# Walrus_Radios.net
KiCad netlist of a schematic drawn in Altium Designer
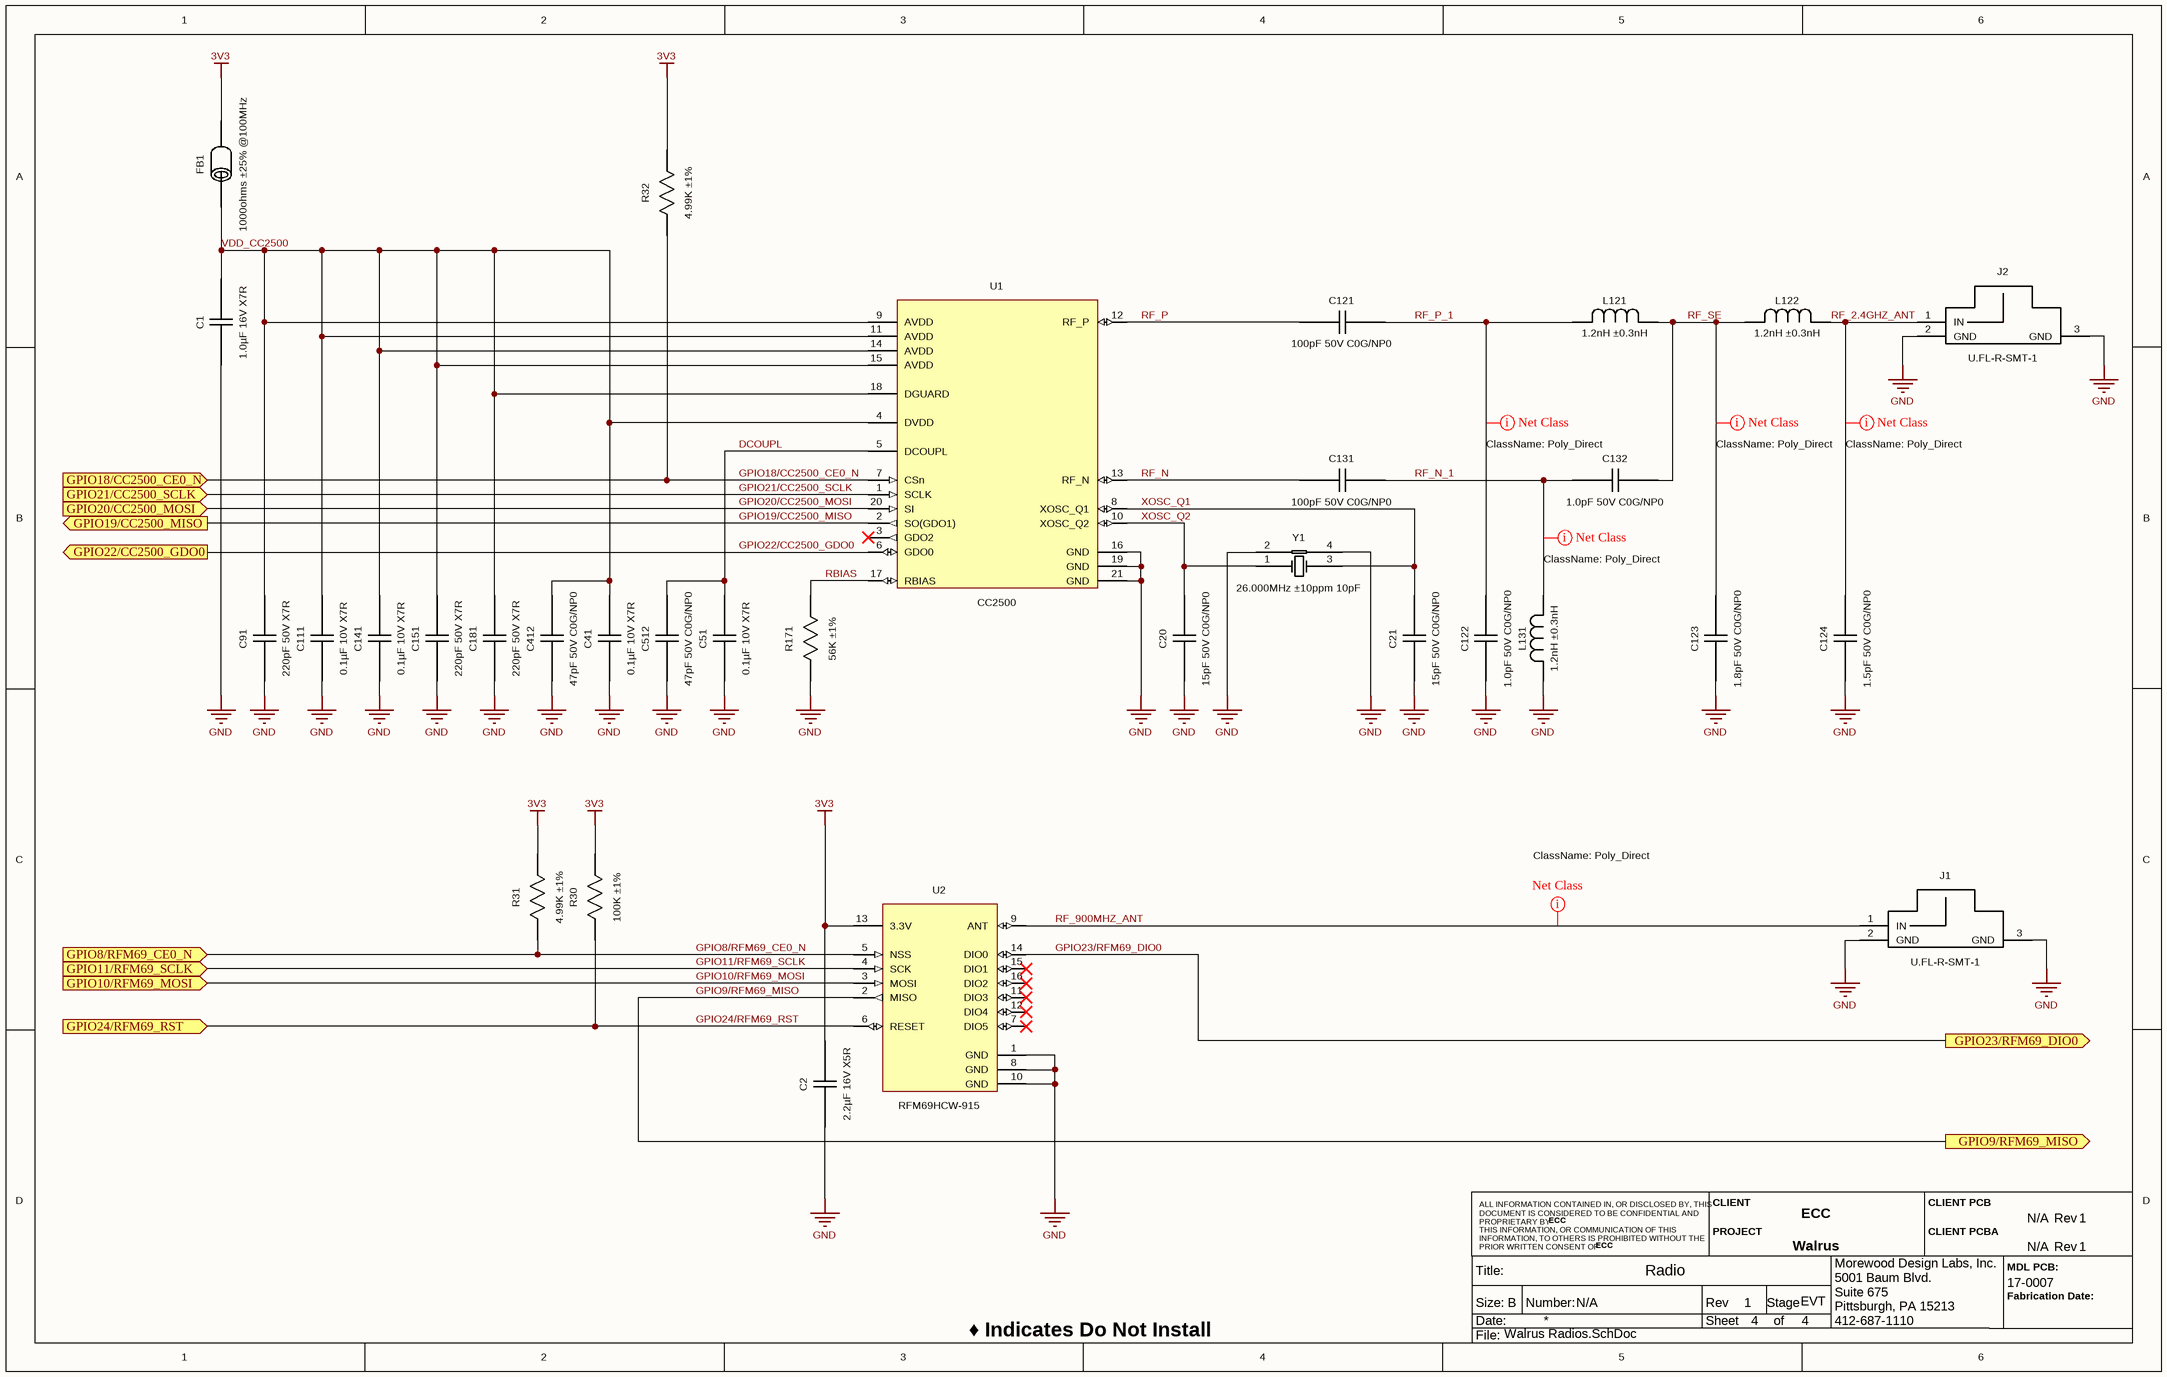
[diagram p0: Walrus Radios.SchDoc]

(export (version "E")
  (design (tool "Eeschema 10.0.6"))
  (components
    (comp (ref "C1")
      (value "1.0µF 16V X7R")
      (footprint "CAPC1608X90L(0603)")
      (description "Ceramic Chip Capacitor")
      (fields
        (field (name "MDLPARTNUMBER") "CAP_000045")
        (field (name "TOLERANCE") "±10%")
        (field (name "CREATOR") "R. Casciola")
      )
      (libsource (lib "Morewood Labs") (part "Capacitor 1"))
    )
    (comp (ref "C2")
      (value "2.2µF 16V X5R")
      (footprint "CAPC1005X60L(0402)")
      (description "Ceramic Chip Capacitor")
      (fields
        (field (name "MDLPARTNUMBER") "CAP_000166")
        (field (name "TOLERANCE") "±10%")
        (field (name "CREATOR") "R. Casciola")
      )
      (libsource (lib "Morewood Labs") (part "Capacitor 1"))
    )
    (comp (ref "C20")
      (value "15pF 50V C0G/NP0")
      (footprint "CAPC1005X60L(0402_FLEXTRONICS)")
      (description "Ceramic Chip Capacitor")
      (fields
        (field (name "MDLPARTNUMBER") "CAP_000179")
        (field (name "TOLERANCE") "±2%")
        (field (name "CREATOR") "R. Casciola")
        (field (name "MODIFER") "R. Casciola")
      )
      (libsource (lib "Morewood Labs") (part "Capacitor 1"))
    )
    (comp (ref "C21")
      (value "15pF 50V C0G/NP0")
      (footprint "CAPC1005X60L(0402_FLEXTRONICS)")
      (description "Ceramic Chip Capacitor")
      (fields
        (field (name "MDLPARTNUMBER") "CAP_000179")
        (field (name "TOLERANCE") "±2%")
        (field (name "CREATOR") "R. Casciola")
        (field (name "MODIFER") "R. Casciola")
      )
      (libsource (lib "Morewood Labs") (part "Capacitor 1"))
    )
    (comp (ref "C41")
      (value "0.1µF 10V X7R")
      (footprint "CAPC1005X60L(0402_FLEXTRONICS)")
      (description "Ceramic Chip Capacitor")
      (fields
        (field (name "MDLPARTNUMBER") "CAP_000208")
        (field (name "TOLERANCE") "±10%")
        (field (name "CREATOR") "R. Casciola")
      )
      (libsource (lib "Morewood Labs") (part "Capacitor 1"))
    )
    (comp (ref "C51")
      (value "0.1µF 10V X7R")
      (footprint "CAPC1005X60L(0402_FLEXTRONICS)")
      (description "Ceramic Chip Capacitor")
      (fields
        (field (name "MDLPARTNUMBER") "CAP_000208")
        (field (name "TOLERANCE") "±10%")
        (field (name "CREATOR") "R. Casciola")
      )
      (libsource (lib "Morewood Labs") (part "Capacitor 1"))
    )
    (comp (ref "C91")
      (value "220pF 50V X7R")
      (footprint "CAPC1005X60L(0402_FLEXTRONICS)")
      (description "Ceramic Chip Capacitor")
      (fields
        (field (name "MDLPARTNUMBER") "CAP_000207")
        (field (name "TOLERANCE") "±10%")
        (field (name "CREATOR") "R. Casciola")
      )
      (libsource (lib "Morewood Labs") (part "Capacitor 1"))
    )
    (comp (ref "C111")
      (value "0.1µF 10V X7R")
      (footprint "CAPC1005X60L(0402_FLEXTRONICS)")
      (description "Ceramic Chip Capacitor")
      (fields
        (field (name "MDLPARTNUMBER") "CAP_000208")
        (field (name "TOLERANCE") "±10%")
        (field (name "CREATOR") "R. Casciola")
      )
      (libsource (lib "Morewood Labs") (part "Capacitor 1"))
    )
    (comp (ref "C121")
      (value "100pF 50V C0G/NP0")
      (footprint "CAPC1005X60L(0402_FLEXTRONICS)")
      (description "Ceramic Chip Capacitor")
      (fields
        (field (name "MDLPARTNUMBER") "CAP_000202")
        (field (name "TOLERANCE") "±5%")
        (field (name "CREATOR") "R. Casciola")
      )
      (libsource (lib "Morewood Labs") (part "Capacitor 1"))
    )
    (comp (ref "C122")
      (value "1.0pF 50V C0G/NP0")
      (footprint "CAPC1005X60L(0402_FLEXTRONICS)")
      (description "Ceramic Chip Capacitor")
      (fields
        (field (name "MDLPARTNUMBER") "CAP_000206")
        (field (name "TOLERANCE") "±0.25pF")
        (field (name "CREATOR") "R. Casciola")
      )
      (libsource (lib "Morewood Labs") (part "Capacitor 1"))
    )
    (comp (ref "C123")
      (value "1.8pF 50V C0G/NP0")
      (footprint "CAPC1005X60L(0402_FLEXTRONICS)")
      (description "Ceramic Chip Capacitor")
      (fields
        (field (name "MDLPARTNUMBER") "CAP_000204")
        (field (name "TOLERANCE") "±0.25pF")
        (field (name "CREATOR") "R. Casciola")
      )
      (libsource (lib "Morewood Labs") (part "Capacitor 1"))
    )
    (comp (ref "C124")
      (value "1.5pF 50V C0G/NP0")
      (footprint "CAPC1005X60L(0402_FLEXTRONICS)")
      (description "Ceramic Chip Capacitor")
      (fields
        (field (name "MDLPARTNUMBER") "CAP_000205")
        (field (name "TOLERANCE") "±0.25pF")
        (field (name "CREATOR") "R. Casciola")
      )
      (libsource (lib "Morewood Labs") (part "Capacitor 1"))
    )
    (comp (ref "C131")
      (value "100pF 50V C0G/NP0")
      (footprint "CAPC1005X60L(0402_FLEXTRONICS)")
      (description "Ceramic Chip Capacitor")
      (fields
        (field (name "MDLPARTNUMBER") "CAP_000202")
        (field (name "TOLERANCE") "±5%")
        (field (name "CREATOR") "R. Casciola")
      )
      (libsource (lib "Morewood Labs") (part "Capacitor 1"))
    )
    (comp (ref "C132")
      (value "1.0pF 50V C0G/NP0")
      (footprint "CAPC1005X60L(0402_FLEXTRONICS)")
      (description "Ceramic Chip Capacitor")
      (fields
        (field (name "MDLPARTNUMBER") "CAP_000206")
        (field (name "TOLERANCE") "±0.25pF")
        (field (name "CREATOR") "R. Casciola")
      )
      (libsource (lib "Morewood Labs") (part "Capacitor 1"))
    )
    (comp (ref "C141")
      (value "0.1µF 10V X7R")
      (footprint "CAPC1005X60L(0402_FLEXTRONICS)")
      (description "Ceramic Chip Capacitor")
      (fields
        (field (name "MDLPARTNUMBER") "CAP_000208")
        (field (name "TOLERANCE") "±10%")
        (field (name "CREATOR") "R. Casciola")
      )
      (libsource (lib "Morewood Labs") (part "Capacitor 1"))
    )
    (comp (ref "C151")
      (value "220pF 50V X7R")
      (footprint "CAPC1005X60L(0402_FLEXTRONICS)")
      (description "Ceramic Chip Capacitor")
      (fields
        (field (name "MDLPARTNUMBER") "CAP_000207")
        (field (name "TOLERANCE") "±10%")
        (field (name "CREATOR") "R. Casciola")
      )
      (libsource (lib "Morewood Labs") (part "Capacitor 1"))
    )
    (comp (ref "C181")
      (value "220pF 50V X7R")
      (footprint "CAPC1005X60L(0402_FLEXTRONICS)")
      (description "Ceramic Chip Capacitor")
      (fields
        (field (name "MDLPARTNUMBER") "CAP_000207")
        (field (name "TOLERANCE") "±10%")
        (field (name "CREATOR") "R. Casciola")
      )
      (libsource (lib "Morewood Labs") (part "Capacitor 1"))
    )
    (comp (ref "C412")
      (value "47pF 50V C0G/NP0")
      (footprint "CAPC1005X60L(0402_FLEXTRONICS)")
      (description "Ceramic Chip Capacitor")
      (fields
        (field (name "MDLPARTNUMBER") "CAP_000193")
        (field (name "TOLERANCE") "±10%")
        (field (name "CREATOR") "R. Casciola")
      )
      (libsource (lib "Morewood Labs") (part "Capacitor 1"))
    )
    (comp (ref "C512")
      (value "47pF 50V C0G/NP0")
      (footprint "CAPC1005X60L(0402_FLEXTRONICS)")
      (description "Ceramic Chip Capacitor")
      (fields
        (field (name "MDLPARTNUMBER") "CAP_000193")
        (field (name "TOLERANCE") "±10%")
        (field (name "CREATOR") "R. Casciola")
      )
      (libsource (lib "Morewood Labs") (part "Capacitor 1"))
    )
    (comp (ref "FB1")
      (value "1000ohms ±25% @100MHz")
      (footprint "FBDC1005X60L(0402)")
      (description "GHz Noise Suppression Chip Ferrite Bead")
      (fields
        (field (name "MDLPARTNUMBER") "FB_000009")
        (field (name "TOLERANCE") "±25%")
        (field (name "CREATOR") "R. Casciola")
      )
      (libsource (lib "Morewood Labs") (part "Ferrite 1"))
    )
    (comp (ref "J1")
      (value "U.FL-R-SMT-1")
      (footprint "HIROSE_U.FL-R-SMT-1")
      (description "Ultra Small Surface Mount Coaxial Connectors - 1.9mm or 2.4mm Mated Height")
      (fields
        (field (name "MDLPARTNUMBER") "CONN_000064")
        (field (name "MFG1PARTNUMBER") "U.FL-R-SMT-1,U.FL-R-SMT-1(10),U.FL-R-SMT-1(40)")
        (field (name "CREATOR") "R. Casciola")
        (field (name "MODIFER") "R. Casciola")
      )
      (libsource (lib "Morewood Labs") (part "U.FL-R-SMT-1"))
    )
    (comp (ref "J2")
      (value "U.FL-R-SMT-1")
      (footprint "HIROSE_U.FL-R-SMT-1")
      (description "Ultra Small Surface Mount Coaxial Connectors - 1.9mm or 2.4mm Mated Height")
      (fields
        (field (name "MDLPARTNUMBER") "CONN_000064")
        (field (name "MFG1PARTNUMBER") "U.FL-R-SMT-1,U.FL-R-SMT-1(10),U.FL-R-SMT-1(40)")
        (field (name "CREATOR") "R. Casciola")
        (field (name "MODIFER") "R. Casciola")
      )
      (libsource (lib "Morewood Labs") (part "U.FL-R-SMT-1"))
    )
    (comp (ref "L121")
      (value "1.2nH ±0.3nH")
      (footprint "INDC1005X60L(0402)")
      (description "Surface Mount Multilayer RF Chip Inductors")
      (fields
        (field (name "MDLPARTNUMBER") "IND_000048")
        (field (name "TOLERANCE") "±0.3nH")
        (field (name "CREATOR") "R. Casciola")
      )
      (libsource (lib "Morewood Labs") (part "Inductor 1"))
    )
    (comp (ref "L122")
      (value "1.2nH ±0.3nH")
      (footprint "INDC1005X60L(0402)")
      (description "Surface Mount Multilayer RF Chip Inductors")
      (fields
        (field (name "MDLPARTNUMBER") "IND_000048")
        (field (name "TOLERANCE") "±0.3nH")
        (field (name "CREATOR") "R. Casciola")
      )
      (libsource (lib "Morewood Labs") (part "Inductor 1"))
    )
    (comp (ref "L131")
      (value "1.2nH ±0.3nH")
      (footprint "INDC1005X60L(0402)")
      (description "Surface Mount Multilayer RF Chip Inductors")
      (fields
        (field (name "MDLPARTNUMBER") "IND_000048")
        (field (name "TOLERANCE") "±0.3nH")
        (field (name "CREATOR") "R. Casciola")
      )
      (libsource (lib "Morewood Labs") (part "Inductor 1"))
    )
    (comp (ref "R30")
      (value "100K ±1%")
      (footprint "RESC1005X40L(0402)")
      (description "Chip Resistor, Thick Film")
      (fields
        (field (name "MDLPARTNUMBER") "RES_000067")
        (field (name "TOLERANCE") "±1%")
        (field (name "CREATOR") "R. Casciola")
      )
      (libsource (lib "Morewood Labs") (part "Resistor 1"))
    )
    (comp (ref "R31")
      (value "4.99K ±1%")
      (footprint "RESC1005X40L(0402)")
      (description "Chip Resistor, Thick Film")
      (fields
        (field (name "MDLPARTNUMBER") "RES_000003")
        (field (name "TOLERANCE") "±1%")
        (field (name "CREATOR") "R. Casciola")
      )
      (libsource (lib "Morewood Labs") (part "Resistor 1"))
    )
    (comp (ref "R32")
      (value "4.99K ±1%")
      (footprint "RESC1005X40L(0402)")
      (description "Chip Resistor, Thick Film")
      (fields
        (field (name "MDLPARTNUMBER") "RES_000003")
        (field (name "TOLERANCE") "±1%")
        (field (name "CREATOR") "R. Casciola")
      )
      (libsource (lib "Morewood Labs") (part "Resistor 1"))
    )
    (comp (ref "R171")
      (value "56K ±1%")
      (footprint "RESC1005X40L(0402)")
      (description "Chip Resistor, Thick Film")
      (fields
        (field (name "MDLPARTNUMBER") "RES_000185")
        (field (name "TOLERANCE") "±1%")
        (field (name "CREATOR") "R. Casciola")
      )
      (libsource (lib "Morewood Labs") (part "Resistor 1"))
    )
    (comp (ref "U1")
      (value "CC2500")
      (footprint "QFN50P400X400X100-21N(CC2500)")
      (description "Low-Cost Low-Power 2.4 GHz RF Transceiver")
      (fields
        (field (name "MDLPARTNUMBER") "IC_000287")
        (field (name "MFG1PARTNUMBER") "CC2500RGP,CC2500RGPR")
        (field (name "CREATOR") "R. Casciola")
      )
      (libsource (lib "Morewood Labs") (part "CC2500"))
    )
    (comp (ref "U2")
      (value "RFM69HCW-915")
      (footprint "RFM69HCW")
      (description "ISM TRANSCEIVER MODULE")
      (fields
        (field (name "MDLPARTNUMBER") "IC_000286")
        (field (name "MFG1PARTNUMBER") "RFM69HCW-915S2")
        (field (name "CREATOR") "R. Casciola")
        (field (name "MODIFER") "R. Casciola")
      )
      (libsource (lib "Morewood Labs") (part "RFM69HCW"))
    )
    (comp (ref "Y1")
      (value "26.000MHz ±10ppm 10pF")
      (footprint "XTAL500X320X110-4N(ABM3B)")
      (description "CERAMIC SMD CRYSTAL")
      (fields
        (field (name "MDLPARTNUMBER") "XTAL_000024")
        (field (name "TOLERANCE") "±10ppm")
        (field (name "CREATOR") "R. Casciola")
      )
      (libsource (lib "Morewood Labs") (part "Crystal 3"))
    )
  )
  (nets
    (net (code "1") (name "/DCOUPL") (class "Default")
      (node (ref "C51") (pin "2") (pinfunction "2_2") (pintype "passive"))
      (node (ref "C512") (pin "2") (pinfunction "2_2") (pintype "passive"))
      (node (ref "U1") (pin "5") (pinfunction "DCOUPL_5") (pintype "power_in"))
    )
    (net (code "2") (name "/GPIO8{slash}RFM69_CE0_N") (class "Default")
      (node (ref "R31") (pin "1") (pinfunction "1_1") (pintype "passive"))
      (node (ref "U2") (pin "5") (pinfunction "NSS_5") (pintype "input"))
    )
    (net (code "3") (name "/GPIO9{slash}RFM69_MISO") (class "Default")
      (node (ref "U2") (pin "2") (pinfunction "MISO_2") (pintype "output"))
    )
    (net (code "4") (name "/GPIO10{slash}RFM69_MOSI") (class "Default")
      (node (ref "U2") (pin "3") (pinfunction "MOSI_3") (pintype "input"))
    )
    (net (code "5") (name "/GPIO11{slash}RFM69_SCLK") (class "Default")
      (node (ref "U2") (pin "4") (pinfunction "SCK_4") (pintype "input"))
    )
    (net (code "6") (name "/GPIO18{slash}CC2500_CE0_N") (class "Default")
      (node (ref "R32") (pin "1") (pinfunction "1_1") (pintype "passive"))
      (node (ref "U1") (pin "7") (pinfunction "CSn_7") (pintype "input"))
    )
    (net (code "7") (name "/GPIO19{slash}CC2500_MISO") (class "Default")
      (node (ref "U1") (pin "2") (pinfunction "SO(GDO1)_2") (pintype "output"))
    )
    (net (code "8") (name "/GPIO20{slash}CC2500_MOSI") (class "Default")
      (node (ref "U1") (pin "20") (pinfunction "SI_20") (pintype "input"))
    )
    (net (code "9") (name "/GPIO21{slash}CC2500_SCLK") (class "Default")
      (node (ref "U1") (pin "1") (pinfunction "SCLK_1") (pintype "input"))
    )
    (net (code "10") (name "/GPIO22{slash}CC2500_GDO0") (class "Default")
      (node (ref "U1") (pin "6") (pinfunction "GDO0_6") (pintype "bidirectional"))
    )
    (net (code "11") (name "/GPIO23{slash}RFM69_DIO0") (class "Default")
      (node (ref "U2") (pin "14") (pinfunction "DIO0_14") (pintype "bidirectional"))
    )
    (net (code "12") (name "/GPIO24{slash}RFM69_RST") (class "Default")
      (node (ref "R30") (pin "1") (pinfunction "1_1") (pintype "passive"))
      (node (ref "U2") (pin "6") (pinfunction "RESET_6") (pintype "bidirectional"))
    )
    (net (code "13") (name "/RBIAS") (class "Default")
      (node (ref "R171") (pin "2") (pinfunction "2_2") (pintype "passive"))
      (node (ref "U1") (pin "17") (pinfunction "RBIAS_17") (pintype "bidirectional"))
    )
    (net (code "14") (name "/RF_2.4GHZ_ANT") (class "Default")
      (node (ref "C124") (pin "2") (pinfunction "2_2") (pintype "passive"))
      (node (ref "J2") (pin "1") (pinfunction "IN_1") (pintype "passive"))
      (node (ref "L122") (pin "2") (pinfunction "2_2") (pintype "passive"))
    )
    (net (code "15") (name "/RF_900MHZ_ANT") (class "Default")
      (node (ref "J1") (pin "1") (pinfunction "IN_1") (pintype "passive"))
      (node (ref "U2") (pin "9") (pinfunction "ANT_9") (pintype "bidirectional"))
    )
    (net (code "16") (name "/RF_N") (class "Default")
      (node (ref "C131") (pin "1") (pinfunction "1_1") (pintype "passive"))
      (node (ref "U1") (pin "13") (pinfunction "RF_N_13") (pintype "bidirectional"))
    )
    (net (code "17") (name "/RF_N_1") (class "Default")
      (node (ref "C131") (pin "2") (pinfunction "2_2") (pintype "passive"))
      (node (ref "C132") (pin "1") (pinfunction "1_1") (pintype "passive"))
      (node (ref "L131") (pin "2") (pinfunction "2_2") (pintype "passive"))
    )
    (net (code "18") (name "/RF_P") (class "Default")
      (node (ref "C121") (pin "1") (pinfunction "1_1") (pintype "passive"))
      (node (ref "U1") (pin "12") (pinfunction "RF_P_12") (pintype "bidirectional"))
    )
    (net (code "19") (name "/RF_P_1") (class "Default")
      (node (ref "C121") (pin "2") (pinfunction "2_2") (pintype "passive"))
      (node (ref "C122") (pin "2") (pinfunction "2_2") (pintype "passive"))
      (node (ref "L121") (pin "1") (pinfunction "1_1") (pintype "passive"))
    )
    (net (code "20") (name "/RF_SE") (class "Default")
      (node (ref "C123") (pin "2") (pinfunction "2_2") (pintype "passive"))
      (node (ref "C132") (pin "2") (pinfunction "2_2") (pintype "passive"))
      (node (ref "L121") (pin "2") (pinfunction "2_2") (pintype "passive"))
      (node (ref "L122") (pin "1") (pinfunction "1_1") (pintype "passive"))
    )
    (net (code "21") (name "/VDD_CC2500") (class "Default")
      (node (ref "C1") (pin "2") (pinfunction "2_2") (pintype "passive"))
      (node (ref "C111") (pin "2") (pinfunction "2_2") (pintype "passive"))
      (node (ref "C141") (pin "2") (pinfunction "2_2") (pintype "passive"))
      (node (ref "C151") (pin "2") (pinfunction "2_2") (pintype "passive"))
      (node (ref "C181") (pin "2") (pinfunction "2_2") (pintype "passive"))
      (node (ref "C41") (pin "2") (pinfunction "2_2") (pintype "passive"))
      (node (ref "C412") (pin "2") (pinfunction "2_2") (pintype "passive"))
      (node (ref "C91") (pin "2") (pinfunction "2_2") (pintype "passive"))
      (node (ref "FB1") (pin "1") (pinfunction "1_1") (pintype "passive"))
      (node (ref "U1") (pin "11") (pinfunction "AVDD_11") (pintype "power_in"))
      (node (ref "U1") (pin "14") (pinfunction "AVDD_14") (pintype "power_in"))
      (node (ref "U1") (pin "15") (pinfunction "AVDD_15") (pintype "power_in"))
      (node (ref "U1") (pin "18") (pinfunction "DGUARD_18") (pintype "power_in"))
      (node (ref "U1") (pin "4") (pinfunction "DVDD_4") (pintype "power_in"))
      (node (ref "U1") (pin "9") (pinfunction "AVDD_9") (pintype "power_in"))
    )
    (net (code "22") (name "/XOSC_Q1") (class "Default")
      (node (ref "C21") (pin "2") (pinfunction "2_2") (pintype "passive"))
      (node (ref "U1") (pin "8") (pinfunction "XOSC_Q1_8") (pintype "bidirectional"))
      (node (ref "Y1") (pin "3") (pinfunction "3_3") (pintype "passive"))
    )
    (net (code "23") (name "/XOSC_Q2") (class "Default")
      (node (ref "C20") (pin "2") (pinfunction "2_2") (pintype "passive"))
      (node (ref "U1") (pin "10") (pinfunction "XOSC_Q2_10") (pintype "bidirectional"))
      (node (ref "Y1") (pin "1") (pinfunction "1_1") (pintype "passive"))
    )
    (net (code "24") (name "3V3") (class "Default")
      (node (ref "C2") (pin "2") (pinfunction "2_2") (pintype "passive"))
      (node (ref "FB1") (pin "2") (pinfunction "2_2") (pintype "passive"))
      (node (ref "R30") (pin "2") (pinfunction "2_2") (pintype "passive"))
      (node (ref "R31") (pin "2") (pinfunction "2_2") (pintype "passive"))
      (node (ref "R32") (pin "2") (pinfunction "2_2") (pintype "passive"))
      (node (ref "U2") (pin "13") (pinfunction "3.3V_13") (pintype "power_in"))
    )
    (net (code "25") (name "GND") (class "Default")
      (node (ref "C1") (pin "1") (pinfunction "1_1") (pintype "passive"))
      (node (ref "C111") (pin "1") (pinfunction "1_1") (pintype "passive"))
      (node (ref "C122") (pin "1") (pinfunction "1_1") (pintype "passive"))
      (node (ref "C123") (pin "1") (pinfunction "1_1") (pintype "passive"))
      (node (ref "C124") (pin "1") (pinfunction "1_1") (pintype "passive"))
      (node (ref "C141") (pin "1") (pinfunction "1_1") (pintype "passive"))
      (node (ref "C151") (pin "1") (pinfunction "1_1") (pintype "passive"))
      (node (ref "C181") (pin "1") (pinfunction "1_1") (pintype "passive"))
      (node (ref "C2") (pin "1") (pinfunction "1_1") (pintype "passive"))
      (node (ref "C20") (pin "1") (pinfunction "1_1") (pintype "passive"))
      (node (ref "C21") (pin "1") (pinfunction "1_1") (pintype "passive"))
      (node (ref "C41") (pin "1") (pinfunction "1_1") (pintype "passive"))
      (node (ref "C412") (pin "1") (pinfunction "1_1") (pintype "passive"))
      (node (ref "C51") (pin "1") (pinfunction "1_1") (pintype "passive"))
      (node (ref "C512") (pin "1") (pinfunction "1_1") (pintype "passive"))
      (node (ref "C91") (pin "1") (pinfunction "1_1") (pintype "passive"))
      (node (ref "J1") (pin "2") (pinfunction "GND_2") (pintype "passive"))
      (node (ref "J1") (pin "3") (pinfunction "GND_3") (pintype "passive"))
      (node (ref "J2") (pin "2") (pinfunction "GND_2") (pintype "passive"))
      (node (ref "J2") (pin "3") (pinfunction "GND_3") (pintype "passive"))
      (node (ref "L131") (pin "1") (pinfunction "1_1") (pintype "passive"))
      (node (ref "R171") (pin "1") (pinfunction "1_1") (pintype "passive"))
      (node (ref "U1") (pin "16") (pinfunction "GND_16") (pintype "power_in"))
      (node (ref "U1") (pin "19") (pinfunction "GND_19") (pintype "power_in"))
      (node (ref "U1") (pin "21") (pinfunction "GND_21") (pintype "power_in"))
      (node (ref "U2") (pin "1") (pinfunction "GND_1") (pintype "power_in"))
      (node (ref "U2") (pin "10") (pinfunction "GND_10") (pintype "power_in"))
      (node (ref "U2") (pin "8") (pinfunction "GND_8") (pintype "power_in"))
      (node (ref "Y1") (pin "2") (pinfunction "2_2") (pintype "passive"))
      (node (ref "Y1") (pin "4") (pinfunction "4_4") (pintype "passive"))
    )
    (net (code "26") (name "unconnected-(U1-GDO2-Pad3)") (class "Default")
      (node (ref "U1") (pin "3") (pinfunction "GDO2_3") (pintype "output+no_connect"))
    )
    (net (code "27") (name "unconnected-(U2-DIO1-Pad15)") (class "Default")
      (node (ref "U2") (pin "15") (pinfunction "DIO1_15") (pintype "bidirectional+no_connect"))
    )
    (net (code "28") (name "unconnected-(U2-DIO2-Pad16)") (class "Default")
      (node (ref "U2") (pin "16") (pinfunction "DIO2_16") (pintype "bidirectional+no_connect"))
    )
    (net (code "29") (name "unconnected-(U2-DIO3-Pad11)") (class "Default")
      (node (ref "U2") (pin "11") (pinfunction "DIO3_11") (pintype "bidirectional+no_connect"))
    )
    (net (code "30") (name "unconnected-(U2-DIO4-Pad12)") (class "Default")
      (node (ref "U2") (pin "12") (pinfunction "DIO4_12") (pintype "bidirectional+no_connect"))
    )
    (net (code "31") (name "unconnected-(U2-DIO5-Pad7)") (class "Default")
      (node (ref "U2") (pin "7") (pinfunction "DIO5_7") (pintype "bidirectional+no_connect"))
    )
  )
)
